# AFE_A.net
KiCad netlist of a schematic drawn in Altium Designer
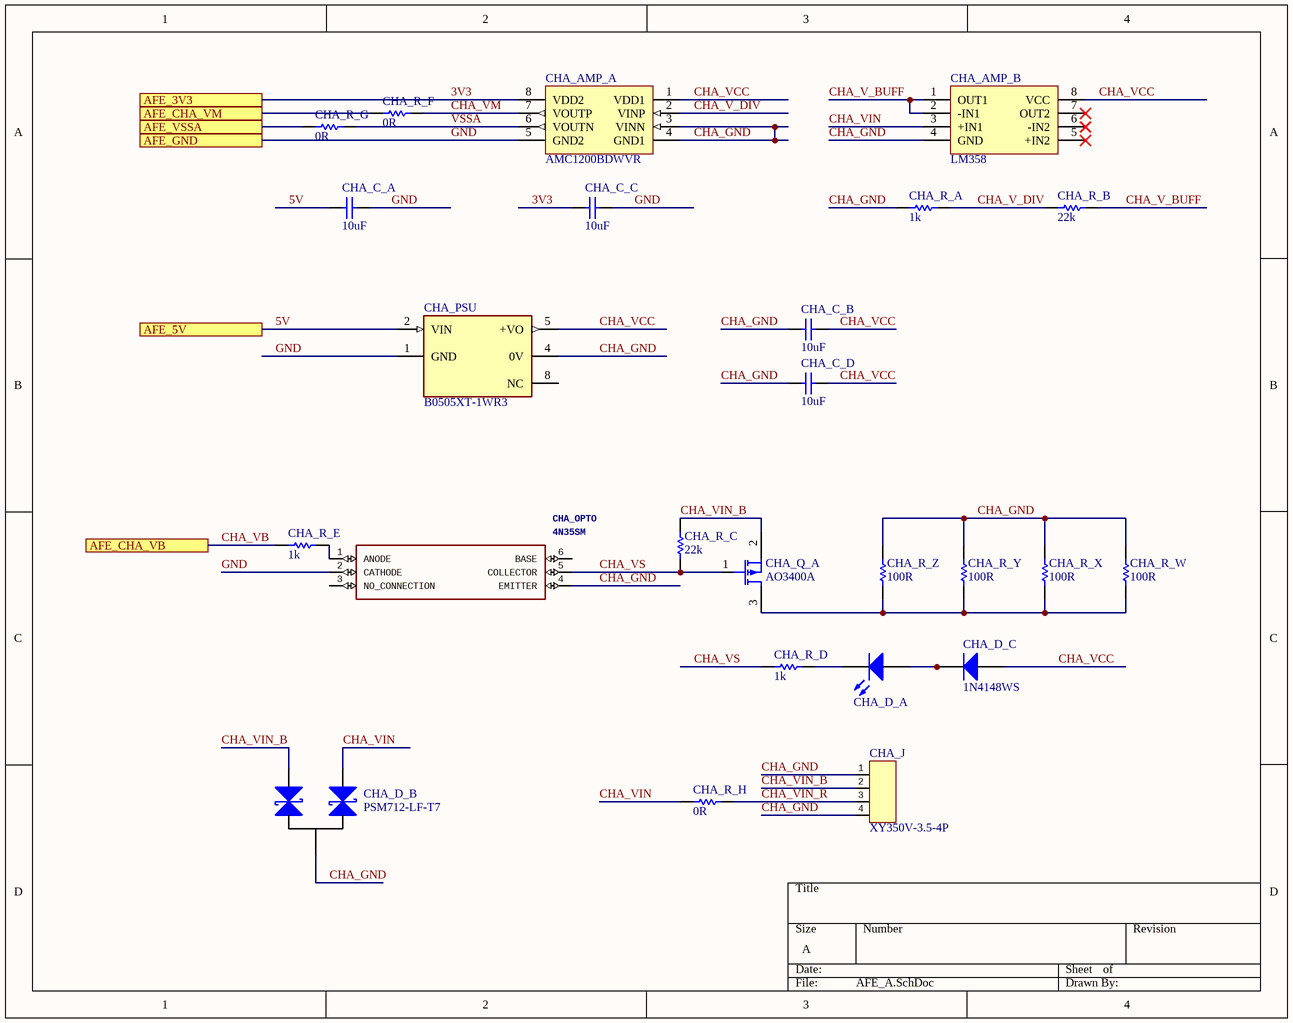
[diagram p0: AFE_A.SchDoc]

(export (version "E")
  (design (tool "Eeschema 10.0.6"))
  (components
    (comp (ref "CHA_AMP_A")
      (value "AMC1200BDWVR")
      (footprint "FOOTPRINTS:SOIC-8-P1.27-W7.5")
      (description "U - IC - 100KHz ISOLATION AMPLIFIER")
      (fields (field (name "LCSC PART #") "C79905"))
      (libsource (lib "JLC_PCB") (part "AMC1200BDWVR"))
    )
    (comp (ref "CHA_AMP_B")
      (value "LM358")
      (footprint "FOOTPRINTS:SOIC-8-P1.27-W3.5")
      (description "U - IC - OP AMP (DUAL)")
      (fields (field (name "LCSC PART #") "C63813"))
      (libsource (lib "JLC_PCB") (part "LMV358IDR"))
    )
    (comp (ref "CHA_C_A")
      (value "10uF")
      (footprint "C_0603")
      (description "C - CAPACITOR - MLCC - 10uF - 25V - 0603")
      (fields (field (name "LCSC PART #") "C96446") (field (name "Comment") "CL10A106MA8NRNC"))
      (libsource (lib "JLC_PCB") (part "CL10A106MA8NRNC"))
    )
    (comp (ref "CHA_C_B")
      (value "10uF")
      (footprint "C_0603")
      (description "C - CAPACITOR - MLCC - 10uF - 25V - 0603")
      (fields (field (name "LCSC PART #") "C96446") (field (name "Comment") "CL10A106MA8NRNC"))
      (libsource (lib "JLC_PCB") (part "CL10A106MA8NRNC"))
    )
    (comp (ref "CHA_C_C")
      (value "10uF")
      (footprint "C_0603")
      (description "C - CAPACITOR - MLCC - 10uF - 25V - 0603")
      (fields (field (name "LCSC PART #") "C96446") (field (name "Comment") "CL10A106MA8NRNC"))
      (libsource (lib "JLC_PCB") (part "CL10A106MA8NRNC"))
    )
    (comp (ref "CHA_C_D")
      (value "10uF")
      (footprint "C_0603")
      (description "C - CAPACITOR - MLCC - 10uF - 25V - 0603")
      (fields (field (name "LCSC PART #") "C96446") (field (name "Comment") "CL10A106MA8NRNC"))
      (libsource (lib "JLC_PCB") (part "CL10A106MA8NRNC"))
    )
    (comp (ref "CHA_D_A")
      (value "KT-0603R")
      (footprint "D_0603")
      (description "D - LED - 0603 - Red")
      (fields (field (name "LCSC PART #") "C2286"))
      (libsource (lib "JLC_PCB") (part "KT-0603R"))
    )
    (comp (ref "CHA_D_B")
      (value "PSM712-LF-T7")
      (footprint "TO-236AB")
      (description "D - DIODE - TVS x2 - 7.2V")
      (fields (field (name "LCSC PART #") "C32677"))
      (libsource (lib "JLC_PCB") (part "PSM712-LF-T7"))
    )
    (comp (ref "CHA_D_C")
      (value "1N4148WS")
      (footprint "SOD-323")
      (description "D - DIODE - FAST TRR - 100V - 150mA - 4ns")
      (fields (field (name "LCSC PART #") "C2128"))
      (libsource (lib "JLC_PCB") (part "1N4148WS"))
    )
    (comp (ref "CHA_J")
      (value "XY350V-3.5-4P")
      (footprint "XY350V-3.5-4P")
      (description "J - JACK - TERMINAL - 4P - RIGHT - MALE")
      (fields (field (name "LCSC PART #") "C557656"))
      (libsource (lib "JLC_PCB") (part "XY350V-3.5-4P"))
    )
    (comp (ref "CHA_OPTO")
      (value "4N35SM")
      (footprint "SOT254P916X508-6N")
      (description "Q - OPTOCOUPLER - 4170 V - 100% CTR")
      (fields (field (name "LCSC PART #") "C258228"))
      (libsource (lib "JLC_PCB") (part "4N35SM"))
    )
    (comp (ref "CHA_PSU")
      (value "B0505XT-1WR3")
      (footprint "CONV_B0512XT-1WR3")
      (description "T - Isolated Module DC DC Converter 5 -> 5V 200mA - DIP")
      (fields (field (name "LCSC PART #") "C19188495") (field (name "MF") "EVISUN"))
      (libsource (lib "JLC_PCB") (part "B0505XT-1WR3"))
    )
    (comp (ref "CHA_Q_A")
      (value "AO3400A")
      (footprint "TO-236AB")
      (description "Q - TRANSISTOR - MOSFET (P) - 20V - 3.4A - 0.26 Ohm")
      (fields (field (name "LCSC PART #") "C20917"))
      (libsource (lib "JLC_PCB") (part "AO3400A"))
    )
    (comp (ref "CHA_R_A")
      (value "1k")
      (footprint "R_0603")
      (description "R - RESISTOR - SMD - 1k - 1% - 0603")
      (fields (field (name "LCSC PART #") "C21190") (field (name "Comment") "0603WAF1001T5E"))
      (libsource (lib "JLC_PCB") (part "0603WAF1001T5E"))
    )
    (comp (ref "CHA_R_B")
      (value "22k")
      (footprint "R_0603")
      (description "R - RESISTOR - SMD - 22k - 1% - 0603")
      (fields (field (name "LCSC PART #") "C31850") (field (name "Comment") "0603WAF2202T5E"))
      (libsource (lib "JLC_PCB") (part "0603WAF2202T5E"))
    )
    (comp (ref "CHA_R_C")
      (value "22k")
      (footprint "R_0603")
      (description "R - RESISTOR - SMD - 22k - 1% - 0603")
      (fields (field (name "LCSC PART #") "C31850") (field (name "Comment") "0603WAF2202T5E"))
      (libsource (lib "JLC_PCB") (part "0603WAF2202T5E"))
    )
    (comp (ref "CHA_R_D")
      (value "1k")
      (footprint "R_0603")
      (description "R - RESISTOR - SMD - 1k - 1% - 0603")
      (fields (field (name "LCSC PART #") "C21190") (field (name "Comment") "0603WAF1001T5E"))
      (libsource (lib "JLC_PCB") (part "0603WAF1001T5E"))
    )
    (comp (ref "CHA_R_E")
      (value "1k")
      (footprint "R_0603")
      (description "R - RESISTOR - SMD - 1k - 1% - 0603")
      (fields (field (name "LCSC PART #") "C21190") (field (name "Comment") "0603WAF1001T5E"))
      (libsource (lib "JLC_PCB") (part "0603WAF1001T5E"))
    )
    (comp (ref "CHA_R_F")
      (value "0R")
      (footprint "R_0603")
      (description "R - RESISTOR - SMD - 0R - 1% - 0603")
      (fields (field (name "LCSC PART #") "C21189") (field (name "Comment") "0603WAF0000T5E"))
      (libsource (lib "JLC_PCB") (part "0603WAF0000T5E"))
    )
    (comp (ref "CHA_R_G")
      (value "0R")
      (footprint "R_0603")
      (description "R - RESISTOR - SMD - 0R - 1% - 0603")
      (fields (field (name "LCSC PART #") "C21189") (field (name "Comment") "0603WAF0000T5E"))
      (libsource (lib "JLC_PCB") (part "0603WAF0000T5E"))
    )
    (comp (ref "CHA_R_H")
      (value "0R")
      (footprint "R_0603")
      (description "R - RESISTOR - SMD - 0R - 1% - 0603")
      (fields (field (name "LCSC PART #") "C21189") (field (name "Comment") "0603WAF0000T5E"))
      (libsource (lib "JLC_PCB") (part "0603WAF0000T5E"))
    )
    (comp (ref "CHA_R_W")
      (value "100R")
      (footprint "R_1206")
      (description "R - RESISTOR - SMD - 100R - 1% - 1206")
      (fields (field (name "LCSC PART #") "C17901") (field (name "Comment") "1206W4F1000T5E"))
      (libsource (lib "JLC_PCB") (part "1206W4F1000T5E"))
    )
    (comp (ref "CHA_R_X")
      (value "100R")
      (footprint "R_1206")
      (description "R - RESISTOR - SMD - 100R - 1% - 1206")
      (fields (field (name "LCSC PART #") "C17901") (field (name "Comment") "1206W4F1000T5E"))
      (libsource (lib "JLC_PCB") (part "1206W4F1000T5E"))
    )
    (comp (ref "CHA_R_Y")
      (value "100R")
      (footprint "R_1206")
      (description "R - RESISTOR - SMD - 100R - 1% - 1206")
      (fields (field (name "LCSC PART #") "C17901") (field (name "Comment") "1206W4F1000T5E"))
      (libsource (lib "JLC_PCB") (part "1206W4F1000T5E"))
    )
    (comp (ref "CHA_R_Z")
      (value "100R")
      (footprint "R_1206")
      (description "R - RESISTOR - SMD - 100R - 1% - 1206")
      (fields (field (name "LCSC PART #") "C17901") (field (name "Comment") "1206W4F1000T5E"))
      (libsource (lib "JLC_PCB") (part "1206W4F1000T5E"))
    )
  )
  (nets
    (net (code "1") (name "/3V3") (class "Default")
      (node (ref "CHA_AMP_A") (pin "8") (pinfunction "VDD2_8") (pintype "passive"))
      (node (ref "CHA_C_C") (pin "2") (pinfunction "2_2") (pintype "passive"))
    )
    (net (code "2") (name "/5V") (class "Default")
      (node (ref "CHA_C_A") (pin "2") (pinfunction "2_2") (pintype "passive"))
      (node (ref "CHA_PSU") (pin "2") (pinfunction "VIN_2") (pintype "input"))
    )
    (net (code "3") (name "/AFE_CHA_VM") (class "Default")
      (node (ref "CHA_R_F") (pin "1") (pinfunction "1_1") (pintype "passive"))
    )
    (net (code "4") (name "/AFE_VSSA") (class "Default")
      (node (ref "CHA_R_G") (pin "1") (pinfunction "1_1") (pintype "passive"))
    )
    (net (code "5") (name "/CHA_GND") (class "Default")
      (node (ref "CHA_AMP_A") (pin "3") (pinfunction "VINN_3") (pintype "input"))
      (node (ref "CHA_AMP_A") (pin "4") (pinfunction "GND1_4") (pintype "power_in"))
      (node (ref "CHA_AMP_B") (pin "4") (pinfunction "GND_4") (pintype "passive"))
      (node (ref "CHA_C_B") (pin "2") (pinfunction "2_2") (pintype "passive"))
      (node (ref "CHA_C_D") (pin "2") (pinfunction "2_2") (pintype "passive"))
      (node (ref "CHA_D_B") (pin "3") (pinfunction "A_3") (pintype "passive"))
      (node (ref "CHA_J") (pin "1") (pinfunction "1_1") (pintype "passive"))
      (node (ref "CHA_J") (pin "4") (pinfunction "4_4") (pintype "passive"))
      (node (ref "CHA_OPTO") (pin "4") (pinfunction "EMITTER_4") (pintype "bidirectional"))
      (node (ref "CHA_PSU") (pin "4") (pinfunction "0V_4") (pintype "passive"))
      (node (ref "CHA_R_A") (pin "1") (pinfunction "1_1") (pintype "passive"))
      (node (ref "CHA_R_W") (pin "1") (pinfunction "1_1") (pintype "passive"))
      (node (ref "CHA_R_X") (pin "1") (pinfunction "1_1") (pintype "passive"))
      (node (ref "CHA_R_Y") (pin "1") (pinfunction "1_1") (pintype "passive"))
      (node (ref "CHA_R_Z") (pin "1") (pinfunction "1_1") (pintype "passive"))
    )
    (net (code "6") (name "/CHA_VB") (class "Default")
      (node (ref "CHA_R_E") (pin "1") (pinfunction "1_1") (pintype "passive"))
    )
    (net (code "7") (name "/CHA_VCC") (class "Default")
      (node (ref "CHA_AMP_A") (pin "1") (pinfunction "VDD1_1") (pintype "passive"))
      (node (ref "CHA_AMP_B") (pin "8") (pinfunction "VCC_8") (pintype "passive"))
      (node (ref "CHA_C_B") (pin "1") (pinfunction "1_1") (pintype "passive"))
      (node (ref "CHA_C_D") (pin "1") (pinfunction "1_1") (pintype "passive"))
      (node (ref "CHA_D_C") (pin "2") (pinfunction "A_2") (pintype "passive"))
      (node (ref "CHA_PSU") (pin "5") (pinfunction "+VO_5") (pintype "output"))
    )
    (net (code "8") (name "/CHA_VIN") (class "Default")
      (node (ref "CHA_AMP_B") (pin "3") (pinfunction "+IN1_3") (pintype "passive"))
      (node (ref "CHA_D_B") (pin "2") (pinfunction "K_2") (pintype "passive"))
      (node (ref "CHA_R_H") (pin "1") (pinfunction "1_1") (pintype "passive"))
    )
    (net (code "9") (name "/CHA_VIN_B") (class "Default")
      (node (ref "CHA_D_B") (pin "1") (pinfunction "K_1") (pintype "passive"))
      (node (ref "CHA_J") (pin "2") (pinfunction "2_2") (pintype "passive"))
      (node (ref "CHA_Q_A") (pin "2") (pinfunction "S_2") (pintype "passive"))
      (node (ref "CHA_R_C") (pin "2") (pinfunction "2_2") (pintype "passive"))
    )
    (net (code "10") (name "/CHA_VIN_R") (class "Default")
      (node (ref "CHA_J") (pin "3") (pinfunction "3_3") (pintype "passive"))
      (node (ref "CHA_R_H") (pin "2") (pinfunction "2_2") (pintype "passive"))
    )
    (net (code "11") (name "/CHA_VM") (class "Default")
      (node (ref "CHA_AMP_A") (pin "7") (pinfunction "VOUTP_7") (pintype "output"))
      (node (ref "CHA_R_F") (pin "2") (pinfunction "2_2") (pintype "passive"))
    )
    (net (code "12") (name "/CHA_VS") (class "Default")
      (node (ref "CHA_OPTO") (pin "5") (pinfunction "COLLECTOR_5") (pintype "bidirectional"))
      (node (ref "CHA_Q_A") (pin "1") (pinfunction "G_1") (pintype "passive"))
      (node (ref "CHA_R_C") (pin "1") (pinfunction "1_1") (pintype "passive"))
      (node (ref "CHA_R_D") (pin "1") (pinfunction "1_1") (pintype "passive"))
    )
    (net (code "13") (name "/CHA_V_BUFF") (class "Default")
      (node (ref "CHA_AMP_B") (pin "1") (pinfunction "OUT1_1") (pintype "passive"))
      (node (ref "CHA_AMP_B") (pin "2") (pinfunction "-IN1_2") (pintype "passive"))
      (node (ref "CHA_R_B") (pin "2") (pinfunction "2_2") (pintype "passive"))
    )
    (net (code "14") (name "/CHA_V_DIV") (class "Default")
      (node (ref "CHA_AMP_A") (pin "2") (pinfunction "VINP_2") (pintype "input"))
      (node (ref "CHA_R_A") (pin "2") (pinfunction "2_2") (pintype "passive"))
      (node (ref "CHA_R_B") (pin "1") (pinfunction "1_1") (pintype "passive"))
    )
    (net (code "15") (name "/GND") (class "Default")
      (node (ref "CHA_AMP_A") (pin "5") (pinfunction "GND2_5") (pintype "power_in"))
      (node (ref "CHA_C_A") (pin "1") (pinfunction "1_1") (pintype "passive"))
      (node (ref "CHA_C_C") (pin "1") (pinfunction "1_1") (pintype "passive"))
      (node (ref "CHA_OPTO") (pin "2") (pinfunction "CATHODE_2") (pintype "bidirectional"))
      (node (ref "CHA_PSU") (pin "1") (pinfunction "GND_1") (pintype "power_in"))
    )
    (net (code "16") (name "/VSSA") (class "Default")
      (node (ref "CHA_AMP_A") (pin "6") (pinfunction "VOUTN_6") (pintype "output"))
      (node (ref "CHA_R_G") (pin "2") (pinfunction "2_2") (pintype "passive"))
    )
    (net (code "17") (name "Net-(CHA_D_A-A)") (class "Default")
      (node (ref "CHA_D_A") (pin "2") (pinfunction "A_2") (pintype "passive"))
      (node (ref "CHA_D_C") (pin "1") (pinfunction "K_1") (pintype "passive"))
    )
    (net (code "18") (name "Net-(CHA_D_A-K)") (class "Default")
      (node (ref "CHA_D_A") (pin "1") (pinfunction "K_1") (pintype "passive"))
      (node (ref "CHA_R_D") (pin "2") (pinfunction "2_2") (pintype "passive"))
    )
    (net (code "19") (name "Net-(CHA_OPTO-ANODE)") (class "Default")
      (node (ref "CHA_OPTO") (pin "1") (pinfunction "ANODE_1") (pintype "bidirectional"))
      (node (ref "CHA_R_E") (pin "2") (pinfunction "2_2") (pintype "passive"))
    )
    (net (code "20") (name "Net-(CHA_Q_A-D)") (class "Default")
      (node (ref "CHA_Q_A") (pin "3") (pinfunction "D_3") (pintype "passive"))
      (node (ref "CHA_R_W") (pin "2") (pinfunction "2_2") (pintype "passive"))
      (node (ref "CHA_R_X") (pin "2") (pinfunction "2_2") (pintype "passive"))
      (node (ref "CHA_R_Y") (pin "2") (pinfunction "2_2") (pintype "passive"))
      (node (ref "CHA_R_Z") (pin "2") (pinfunction "2_2") (pintype "passive"))
    )
    (net (code "21") (name "unconnected-(CHA_AMP_B-+IN2-Pad5)") (class "Default")
      (node (ref "CHA_AMP_B") (pin "5") (pinfunction "+IN2_5") (pintype "passive+no_connect"))
    )
    (net (code "22") (name "unconnected-(CHA_AMP_B--IN2-Pad6)") (class "Default")
      (node (ref "CHA_AMP_B") (pin "6") (pinfunction "-IN2_6") (pintype "passive+no_connect"))
    )
    (net (code "23") (name "unconnected-(CHA_AMP_B-OUT2-Pad7)") (class "Default")
      (node (ref "CHA_AMP_B") (pin "7") (pinfunction "OUT2_7") (pintype "passive+no_connect"))
    )
    (net (code "24") (name "unconnected-(CHA_OPTO-BASE-Pad6)") (class "Default")
      (node (ref "CHA_OPTO") (pin "6") (pinfunction "BASE_6") (pintype "bidirectional"))
    )
    (net (code "25") (name "unconnected-(CHA_OPTO-NO_CONNECTION-Pad3)") (class "Default")
      (node (ref "CHA_OPTO") (pin "3") (pinfunction "NO_CONNECTION_3") (pintype "bidirectional"))
    )
    (net (code "26") (name "unconnected-(CHA_PSU-NC-Pad8)") (class "Default")
      (node (ref "CHA_PSU") (pin "8") (pinfunction "NC_8") (pintype "passive"))
    )
  )
)
